# Industrial_Serial_Comm.net
KiCad netlist of a schematic drawn in Altium Designer
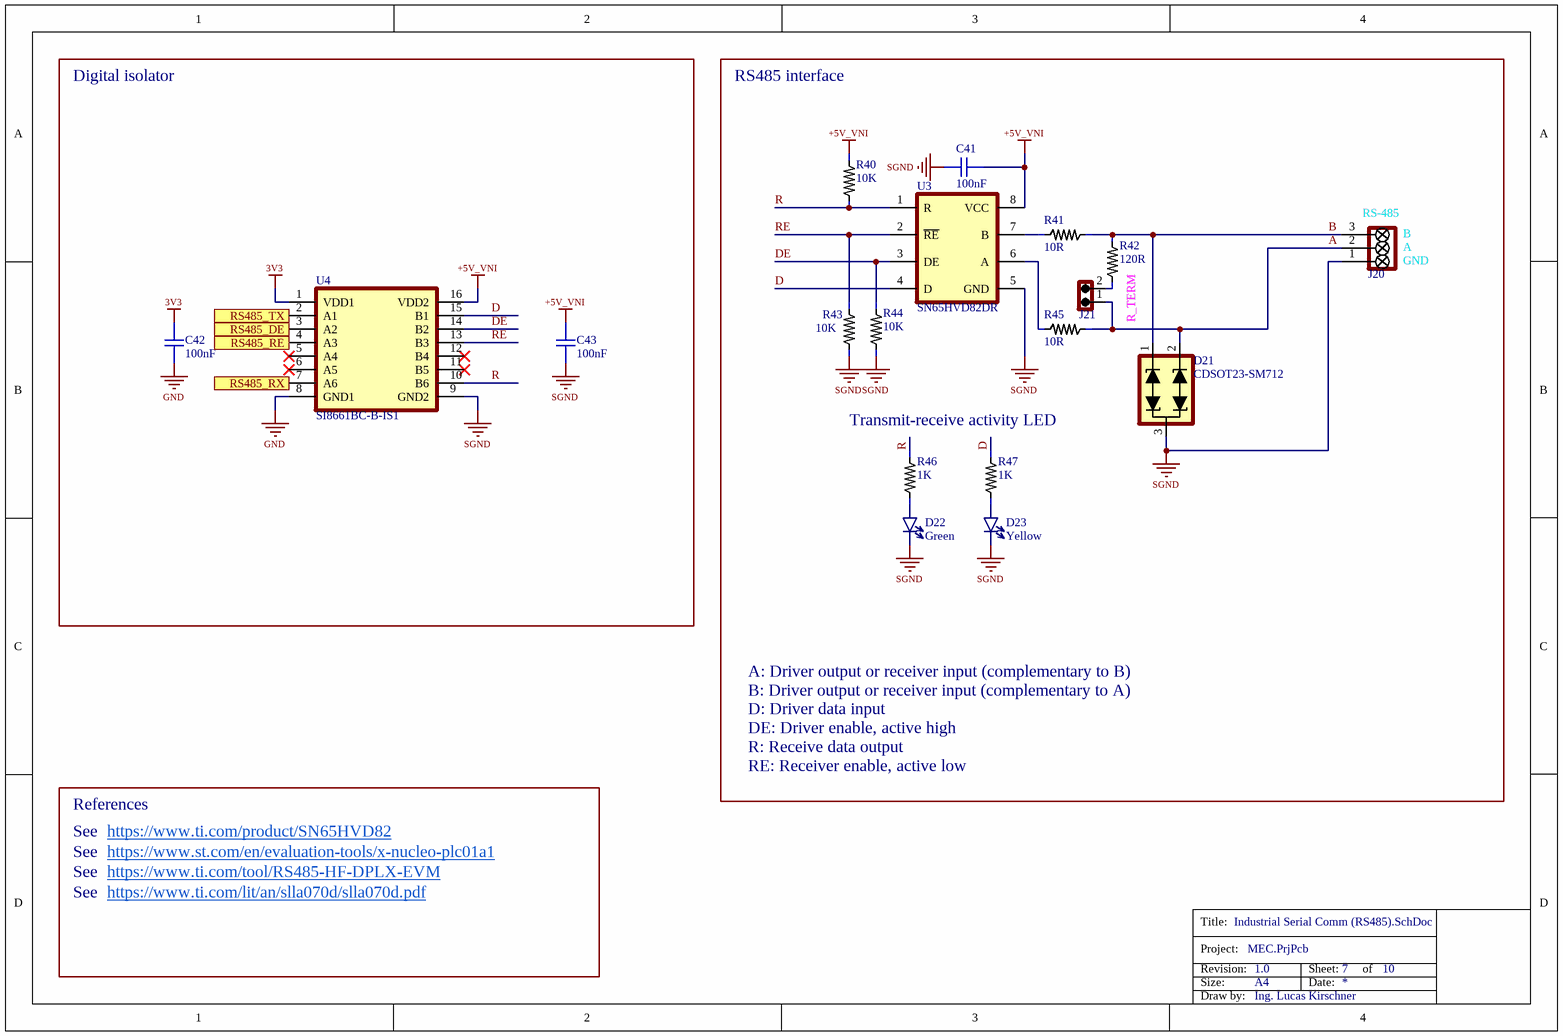
[diagram p0: Industrial Serial Comm (RS485).SchDoc]

(export (version "E")
  (design (tool "Eeschema 10.0.6"))
  (components
    (comp (ref "C41")
      (value "100nF")
      (footprint "CAPC1005N")
      (description "Multilayer Ceramic Capacitors MLCC - SMD/SMT 50 V 0.1uF X7R 0402 10%")
      (fields (field (name "PART NUMBER") "CC0402KRX5R9BB104") (field (name "MANUFACTURER") "YAGEO"))
      (libsource (lib "SchLib") (part "C-MLCC-100nF-50V-10%-0402"))
    )
    (comp (ref "C42")
      (value "100nF")
      (footprint "CAPC1005N")
      (description "Multilayer Ceramic Capacitors MLCC - SMD/SMT 50 V 0.1uF X7R 0402 10%")
      (fields (field (name "PART NUMBER") "CC0402KRX5R9BB104") (field (name "MANUFACTURER") "YAGEO"))
      (libsource (lib "SchLib") (part "C-MLCC-100nF-50V-10%-0402"))
    )
    (comp (ref "C43")
      (value "100nF")
      (footprint "CAPC1005N")
      (description "Multilayer Ceramic Capacitors MLCC - SMD/SMT 50 V 0.1uF X7R 0402 10%")
      (fields (field (name "PART NUMBER") "CC0402KRX5R9BB104") (field (name "MANUFACTURER") "YAGEO"))
      (libsource (lib "SchLib") (part "C-MLCC-100nF-50V-10%-0402"))
    )
    (comp (ref "D21")
      (value "ESD Protection Diodes")
      (footprint "SOT95P230X117-3N")
      (description "ESD Protection Diodes / TVS Diodes SOT-23 7V400W Low Capacitance")
      (fields
        (field (name "MANUFACTURER") "Bourns")
        (field (name "MOUSER PART #") "652-CDSOT23-SM712")
        (field (name "PART NUMBER") "CDSOT23-SM712")
      )
      (libsource (lib "SchLib") (part "D-CDSOT23-SM712"))
    )
    (comp (ref "D22")
      (value "Green")
      (footprint "LEDC1608X80N_GREEN")
      (description "Standard Single Color LEDs 0603 Green")
      (fields (field (name "PART NUMBER") "LTST-C190KGKT") (field (name "MANUFACTURER") "LITEON"))
      (libsource (lib "SchLib") (part "D-LED-GREEN-2V-20mA-0603"))
    )
    (comp (ref "D23")
      (value "Yellow")
      (footprint "LEDC1608X80N_YELLOW")
      (description "Standard Single Color LEDs 0603 Yellow")
      (fields (field (name "PART NUMBER") "LTST-C190KSKT") (field (name "MANUFACTURER") "LITEON"))
      (libsource (lib "SchLib") (part "D-LED-YELLOW-2V-20mA-0603"))
    )
    (comp (ref "J20")
      (value "Terminal Blocks")
      (footprint "CONB_FIX508P-3N")
      (description "Pluggable Terminal Blocks 3 Pos 5.08mm pitch Through Hole Header")
      (fields (field (name "MOUSER PART #") "737-EBA-03-D-BU-01") (field (name "MANUFACTURER") "Adam Tech"))
      (libsource (lib "SchLib") (part "J-03-5P08-TERM-F-VERT-TH"))
    )
    (comp (ref "J21")
      (value "Male straight header")
      (footprint "CONH_ML254P-2N")
      (description "Male straight header, 1 row, 2 positions, 2.54mm pitch, through-hole")
      (fields (field (name "PART NUMBER") "10129378-902001BLF") (field (name "MANUFACTURER") "Amphenol FCI"))
      (libsource (lib "SchLib") (part "J-02-2P54-HDR-M-VERT-TH"))
    )
    (comp (ref "R40")
      (value "10K")
      (footprint "RESC1005N")
      (description "Thick Film Resistors - SMD General Purpose Chip Resistor 0402, 10kOhms, 1%, 1/16W")
      (fields (field (name "PART NUMBER") "RC0402FR-0710KL") (field (name "MANUFACTURER") "YAGEO"))
      (libsource (lib "SchLib") (part "R-THICK-10K-62.5mW-1%-0402"))
    )
    (comp (ref "R41")
      (value "10R")
      (footprint "RESC2012N")
      (description "Thick Film Resistors - SMD High Power Chip Resistor 0805, 10Ohms, 1%, 1/2W")
      (fields (field (name "PART NUMBER") "CRCW080510R0FKEAHP") (field (name "MANUFACTURER") "Vishay"))
      (libsource (lib "SchLib") (part "R-THICK-HP-10R-500mW-1%-0805"))
    )
    (comp (ref "R42")
      (value "120R")
      (footprint "RESC1005N")
      (description "Thick Film Resistors - SMD General Purpose Chip Resistor 0402, 120Ohms, 1%, 1/16W")
      (fields (field (name "PART NUMBER") "RC0402FR-07120RL") (field (name "MANUFACTURER") "YAGEO"))
      (libsource (lib "SchLib") (part "R-THICK-120R-62.5mW-1%-0402"))
    )
    (comp (ref "R43")
      (value "10K")
      (footprint "RESC1005N")
      (description "Thick Film Resistors - SMD General Purpose Chip Resistor 0402, 10kOhms, 1%, 1/16W")
      (fields (field (name "PART NUMBER") "RC0402FR-0710KL") (field (name "MANUFACTURER") "YAGEO"))
      (libsource (lib "SchLib") (part "R-THICK-10K-62.5mW-1%-0402"))
    )
    (comp (ref "R44")
      (value "10K")
      (footprint "RESC1005N")
      (description "Thick Film Resistors - SMD General Purpose Chip Resistor 0402, 10kOhms, 1%, 1/16W")
      (fields (field (name "PART NUMBER") "RC0402FR-0710KL") (field (name "MANUFACTURER") "YAGEO"))
      (libsource (lib "SchLib") (part "R-THICK-10K-62.5mW-1%-0402"))
    )
    (comp (ref "R45")
      (value "10R")
      (footprint "RESC2012N")
      (description "Thick Film Resistors - SMD High Power Chip Resistor 0805, 10Ohms, 1%, 1/2W")
      (fields (field (name "PART NUMBER") "CRCW080510R0FKEAHP") (field (name "MANUFACTURER") "Vishay"))
      (libsource (lib "SchLib") (part "R-THICK-HP-10R-500mW-1%-0805"))
    )
    (comp (ref "R46")
      (value "1K")
      (footprint "RESC1005N")
      (description "Thick Film Resistors - SMD General Purpose Chip Resistor 0402, 1kOhms, 1%, 1/16W")
      (fields (field (name "PART NUMBER") "RC0402FR-071KL") (field (name "MANUFACTURER") "YAGEO"))
      (libsource (lib "SchLib") (part "R-THICK-1K-62.5mW-1%-0402"))
    )
    (comp (ref "R47")
      (value "1K")
      (footprint "RESC1005N")
      (description "Thick Film Resistors - SMD General Purpose Chip Resistor 0402, 1kOhms, 1%, 1/16W")
      (fields (field (name "PART NUMBER") "RC0402FR-071KL") (field (name "MANUFACTURER") "YAGEO"))
      (libsource (lib "SchLib") (part "R-THICK-1K-62.5mW-1%-0402"))
    )
    (comp (ref "U3")
      (value "RS-485 Interface")
      (footprint "SOIC127P600X175-8N")
      (description "RS-485 Interface IC 5V-Supply")
      (fields
        (field (name "MANUFACTURER") "Texas Instruments")
        (field (name "PART NUMBER") "SN65HVD82DR")
        (field (name "MOUSER PART #") "595-SN65HVD82DR")
      )
      (libsource (lib "SchLib") (part "U-SN65HVD82DR"))
    )
    (comp (ref "U4")
      (value "Digital Isolators")
      (footprint "SOIC127P1030X265-16N")
      (description "Digital Isolators 3.75 kV 5 forward & 1 reverse 6-channel isolator")
      (fields
        (field (name "MANUFACTURER") "Skyworks")
        (field (name "PART NUMBER") "SI8661BC-B-IS1")
        (field (name "MOUSER PART #") "634-SI8661BC-B-IS1")
      )
      (libsource (lib "SchLib") (part "U-SI8661BC-B-IS1"))
    )
  )
  (nets
    (net (code "1") (name "+5V_VNI") (class "Default")
      (node (ref "C41") (pin "1") (pinfunction "1_1") (pintype "passive"))
      (node (ref "C43") (pin "1") (pinfunction "1_1") (pintype "passive"))
      (node (ref "R40") (pin "2") (pinfunction "2_2") (pintype "passive"))
      (node (ref "U3") (pin "8") (pinfunction "VCC_8") (pintype "passive"))
      (node (ref "U4") (pin "16") (pinfunction "VDD2_16") (pintype "passive"))
    )
    (net (code "2") (name "/A") (class "Default")
      (node (ref "D21") (pin "2") (pinfunction "2_2") (pintype "passive"))
      (node (ref "J20") (pin "2") (pinfunction "2_2") (pintype "passive"))
      (node (ref "J21") (pin "1") (pinfunction "1_1") (pintype "passive"))
      (node (ref "R45") (pin "2") (pinfunction "2_2") (pintype "passive"))
    )
    (net (code "3") (name "/B") (class "Default")
      (node (ref "D21") (pin "1") (pinfunction "1_1") (pintype "passive"))
      (node (ref "J20") (pin "3") (pinfunction "3_3") (pintype "passive"))
      (node (ref "R41") (pin "2") (pinfunction "2_2") (pintype "passive"))
      (node (ref "R42") (pin "2") (pinfunction "2_2") (pintype "passive"))
    )
    (net (code "4") (name "/D") (class "Default")
      (node (ref "R47") (pin "2") (pinfunction "2_2") (pintype "passive"))
      (node (ref "U3") (pin "4") (pinfunction "D_4") (pintype "passive"))
      (node (ref "U4") (pin "15") (pinfunction "B1_15") (pintype "passive"))
    )
    (net (code "5") (name "/DE") (class "Default")
      (node (ref "R44") (pin "2") (pinfunction "2_2") (pintype "passive"))
      (node (ref "U3") (pin "3") (pinfunction "DE_3") (pintype "passive"))
      (node (ref "U4") (pin "14") (pinfunction "B2_14") (pintype "passive"))
    )
    (net (code "6") (name "/R") (class "Default")
      (node (ref "R40") (pin "1") (pinfunction "1_1") (pintype "passive"))
      (node (ref "R46") (pin "2") (pinfunction "2_2") (pintype "passive"))
      (node (ref "U3") (pin "1") (pinfunction "R_1") (pintype "passive"))
      (node (ref "U4") (pin "10") (pinfunction "B6_10") (pintype "passive"))
    )
    (net (code "7") (name "/RE") (class "Default")
      (node (ref "R43") (pin "2") (pinfunction "2_2") (pintype "passive"))
      (node (ref "U3") (pin "2") (pinfunction "~{RE}_2") (pintype "passive"))
      (node (ref "U4") (pin "13") (pinfunction "B3_13") (pintype "passive"))
    )
    (net (code "8") (name "/RS485_DE") (class "Default")
      (node (ref "U4") (pin "3") (pinfunction "A2_3") (pintype "passive"))
    )
    (net (code "9") (name "/RS485_RE") (class "Default")
      (node (ref "U4") (pin "4") (pinfunction "A3_4") (pintype "passive"))
    )
    (net (code "10") (name "/RS485_RX") (class "Default")
      (node (ref "U4") (pin "7") (pinfunction "A6_7") (pintype "passive"))
    )
    (net (code "11") (name "/RS485_TX") (class "Default")
      (node (ref "U4") (pin "2") (pinfunction "A1_2") (pintype "passive"))
    )
    (net (code "12") (name "3V3") (class "Default")
      (node (ref "C42") (pin "1") (pinfunction "1_1") (pintype "passive"))
      (node (ref "U4") (pin "1") (pinfunction "VDD1_1") (pintype "passive"))
    )
    (net (code "13") (name "GND") (class "Default")
      (node (ref "C42") (pin "2") (pinfunction "2_2") (pintype "passive"))
      (node (ref "U4") (pin "8") (pinfunction "GND1_8") (pintype "passive"))
    )
    (net (code "14") (name "Net-(D22-PadA)") (class "Default")
      (node (ref "D22") (pin "A") (pinfunction "A_A") (pintype "passive"))
      (node (ref "R46") (pin "1") (pinfunction "1_1") (pintype "passive"))
    )
    (net (code "15") (name "Net-(D23-PadA)") (class "Default")
      (node (ref "D23") (pin "A") (pinfunction "A_A") (pintype "passive"))
      (node (ref "R47") (pin "1") (pinfunction "1_1") (pintype "passive"))
    )
    (net (code "16") (name "Net-(J21-Pad2)") (class "Default")
      (node (ref "J21") (pin "2") (pinfunction "2_2") (pintype "passive"))
      (node (ref "R42") (pin "1") (pinfunction "1_1") (pintype "passive"))
    )
    (net (code "17") (name "Net-(U3-A)") (class "Default")
      (node (ref "R45") (pin "1") (pinfunction "1_1") (pintype "passive"))
      (node (ref "U3") (pin "6") (pinfunction "A_6") (pintype "passive"))
    )
    (net (code "18") (name "Net-(U3-B)") (class "Default")
      (node (ref "R41") (pin "1") (pinfunction "1_1") (pintype "passive"))
      (node (ref "U3") (pin "7") (pinfunction "B_7") (pintype "passive"))
    )
    (net (code "19") (name "SGND") (class "Default")
      (node (ref "C41") (pin "2") (pinfunction "2_2") (pintype "passive"))
      (node (ref "C43") (pin "2") (pinfunction "2_2") (pintype "passive"))
      (node (ref "D21") (pin "3") (pinfunction "3_3") (pintype "passive"))
      (node (ref "D22") (pin "C") (pinfunction "C_C") (pintype "passive"))
      (node (ref "D23") (pin "C") (pinfunction "C_C") (pintype "passive"))
      (node (ref "J20") (pin "1") (pinfunction "1_1") (pintype "passive"))
      (node (ref "R43") (pin "1") (pinfunction "1_1") (pintype "passive"))
      (node (ref "R44") (pin "1") (pinfunction "1_1") (pintype "passive"))
      (node (ref "U3") (pin "5") (pinfunction "GND_5") (pintype "passive"))
      (node (ref "U4") (pin "9") (pinfunction "GND2_9") (pintype "passive"))
    )
    (net (code "20") (name "unconnected-(U4-A4-Pad5)") (class "Default")
      (node (ref "U4") (pin "5") (pinfunction "A4_5") (pintype "passive+no_connect"))
    )
    (net (code "21") (name "unconnected-(U4-A5-Pad6)") (class "Default")
      (node (ref "U4") (pin "6") (pinfunction "A5_6") (pintype "passive+no_connect"))
    )
    (net (code "22") (name "unconnected-(U4-B4-Pad12)") (class "Default")
      (node (ref "U4") (pin "12") (pinfunction "B4_12") (pintype "passive+no_connect"))
    )
    (net (code "23") (name "unconnected-(U4-B5-Pad11)") (class "Default")
      (node (ref "U4") (pin "11") (pinfunction "B5_11") (pintype "passive+no_connect"))
    )
  )
)
